# Sheet1.net
KiCad netlist of a schematic drawn in Altium Designer
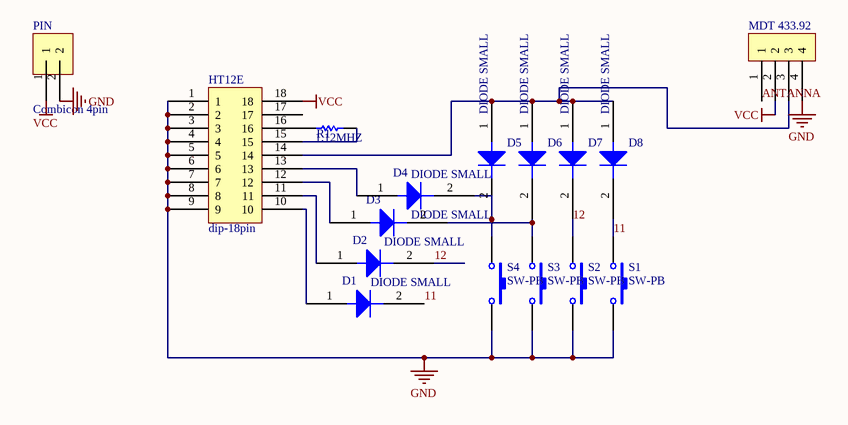
[diagram p0: Sheet1.SchDoc]

(export (version "E")
  (design (tool "Eeschema 10.0.6"))
  (components
    (comp (ref "D1")
      (value "DIODE SMALL")
      (footprint "diode small")
      (libsource (lib "Devindia_v4.0") (part "DIODE SMALL"))
    )
    (comp (ref "D2")
      (value "DIODE SMALL")
      (footprint "diode small")
      (libsource (lib "Devindia_v4.0") (part "DIODE SMALL"))
    )
    (comp (ref "D3")
      (value "DIODE SMALL")
      (footprint "diode small")
      (libsource (lib "Devindia_v4.0") (part "DIODE SMALL"))
    )
    (comp (ref "D4")
      (value "DIODE SMALL")
      (footprint "diode small")
      (libsource (lib "Devindia_v4.0") (part "DIODE SMALL"))
    )
    (comp (ref "D5")
      (value "DIODE SMALL")
      (footprint "diode small")
      (libsource (lib "Devindia_v4.0") (part "DIODE SMALL"))
    )
    (comp (ref "D6")
      (value "DIODE SMALL")
      (footprint "diode small")
      (libsource (lib "Devindia_v4.0") (part "DIODE SMALL"))
    )
    (comp (ref "D7")
      (value "DIODE SMALL")
      (footprint "diode small")
      (libsource (lib "Devindia_v4.0") (part "DIODE SMALL"))
    )
    (comp (ref "D8")
      (value "DIODE SMALL")
      (footprint "diode small")
      (libsource (lib "Devindia_v4.0") (part "DIODE SMALL"))
    )
    (comp (ref "HT12E")
      (value "dip-18pin")
      (footprint "dip-18pin")
      (libsource (lib "Devindia_v4.0") (part "dip-18pin"))
    )
    (comp (ref "MDT 433.92")
      (value "~")
      (footprint "PCBComponent_1")
      (libsource (lib "Schlib1") (part "Component_1"))
    )
    (comp (ref "PIN")
      (value "Combicon 4pin")
      (footprint "combicon-2pin_black")
      (libsource (lib "Devindia_v4.0") (part "Combicon - 2 pin_black"))
    )
    (comp (ref "R1")
      (value "1.12MHZ")
      (footprint "res- 2.54x3")
      (libsource (lib "Devindia_v4.0") (part "Resistor 2.54x3"))
    )
    (comp (ref "S1")
      (value "SW-PB")
      (footprint "sw-pb")
      (description "Switch")
      (fields (field (name "PUBLISHER") "Altium Limited"))
      (libsource (lib "Devindia_v4.0") (part "SW-PB"))
    )
    (comp (ref "S2")
      (value "SW-PB")
      (footprint "sw-pb")
      (description "Switch")
      (fields (field (name "PUBLISHER") "Altium Limited"))
      (libsource (lib "Devindia_v4.0") (part "SW-PB"))
    )
    (comp (ref "S3")
      (value "SW-PB")
      (footprint "sw-pb")
      (description "Switch")
      (fields (field (name "PUBLISHER") "Altium Limited"))
      (libsource (lib "Devindia_v4.0") (part "SW-PB"))
    )
    (comp (ref "S4")
      (value "SW-PB")
      (footprint "sw-pb")
      (description "Switch")
      (fields (field (name "PUBLISHER") "Altium Limited"))
      (libsource (lib "Devindia_v4.0") (part "SW-PB"))
    )
  )
  (nets
    (net (code "1") (name "/11") (class "Default")
      (node (ref "D1") (pin "2") (pinfunction "1_2") (pintype "passive"))
      (node (ref "D8") (pin "2") (pinfunction "1_2") (pintype "passive"))
      (node (ref "S1") (pin "1") (pinfunction "1_1") (pintype "passive"))
    )
    (net (code "2") (name "/12") (class "Default")
      (node (ref "D2") (pin "2") (pinfunction "1_2") (pintype "passive"))
      (node (ref "D7") (pin "2") (pinfunction "1_2") (pintype "passive"))
      (node (ref "S2") (pin "1") (pinfunction "1_1") (pintype "passive"))
    )
    (net (code "3") (name "/ANTANNA") (class "Default")
      (node (ref "MDT 433.92") (pin "1") (pinfunction "1_1") (pintype "passive"))
    )
    (net (code "4") (name "GND") (class "Default")
      (node (ref "HT12E") (pin "1") (pinfunction "1_1") (pintype "passive"))
      (node (ref "HT12E") (pin "2") (pinfunction "2_2") (pintype "passive"))
      (node (ref "HT12E") (pin "3") (pinfunction "3_3") (pintype "passive"))
      (node (ref "HT12E") (pin "4") (pinfunction "4_4") (pintype "passive"))
      (node (ref "HT12E") (pin "5") (pinfunction "5_5") (pintype "passive"))
      (node (ref "HT12E") (pin "6") (pinfunction "6_6") (pintype "passive"))
      (node (ref "HT12E") (pin "7") (pinfunction "7_7") (pintype "passive"))
      (node (ref "HT12E") (pin "8") (pinfunction "8_8") (pintype "passive"))
      (node (ref "HT12E") (pin "9") (pinfunction "9_9") (pintype "passive"))
      (node (ref "MDT 433.92") (pin "4") (pinfunction "4_4") (pintype "passive"))
      (node (ref "PIN") (pin "2") (pinfunction "2_2") (pintype "passive"))
      (node (ref "S1") (pin "2") (pinfunction "2_2") (pintype "passive"))
      (node (ref "S2") (pin "2") (pinfunction "2_2") (pintype "passive"))
      (node (ref "S3") (pin "2") (pinfunction "2_2") (pintype "passive"))
      (node (ref "S4") (pin "2") (pinfunction "2_2") (pintype "passive"))
    )
    (net (code "5") (name "Net-(D1-Pad1)") (class "Default")
      (node (ref "D1") (pin "1") (pinfunction "1_1") (pintype "passive"))
      (node (ref "HT12E") (pin "10") (pinfunction "10_10") (pintype "passive"))
    )
    (net (code "6") (name "Net-(D2-Pad1)") (class "Default")
      (node (ref "D2") (pin "1") (pinfunction "1_1") (pintype "passive"))
      (node (ref "HT12E") (pin "11") (pinfunction "11_11") (pintype "passive"))
    )
    (net (code "7") (name "Net-(D3-1-Pad2)") (class "Default")
      (node (ref "D3") (pin "2") (pinfunction "1_2") (pintype "passive"))
      (node (ref "D6") (pin "2") (pinfunction "1_2") (pintype "passive"))
      (node (ref "S3") (pin "1") (pinfunction "1_1") (pintype "passive"))
    )
    (net (code "8") (name "Net-(D3-Pad1)") (class "Default")
      (node (ref "D3") (pin "1") (pinfunction "1_1") (pintype "passive"))
      (node (ref "HT12E") (pin "12") (pinfunction "12_12") (pintype "passive"))
    )
    (net (code "9") (name "Net-(D4-1-Pad2)") (class "Default")
      (node (ref "D4") (pin "2") (pinfunction "1_2") (pintype "passive"))
      (node (ref "D5") (pin "2") (pinfunction "1_2") (pintype "passive"))
      (node (ref "S4") (pin "1") (pinfunction "1_1") (pintype "passive"))
    )
    (net (code "10") (name "Net-(D4-Pad1)") (class "Default")
      (node (ref "D4") (pin "1") (pinfunction "1_1") (pintype "passive"))
      (node (ref "HT12E") (pin "13") (pinfunction "13_13") (pintype "passive"))
    )
    (net (code "11") (name "Net-(D5-Pad1)") (class "Default")
      (node (ref "D5") (pin "1") (pinfunction "1_1") (pintype "passive"))
      (node (ref "D6") (pin "1") (pinfunction "1_1") (pintype "passive"))
      (node (ref "D7") (pin "1") (pinfunction "1_1") (pintype "passive"))
      (node (ref "D8") (pin "1") (pinfunction "1_1") (pintype "passive"))
      (node (ref "HT12E") (pin "14") (pinfunction "14_14") (pintype "passive"))
      (node (ref "MDT 433.92") (pin "3") (pinfunction "3_3") (pintype "passive"))
    )
    (net (code "12") (name "Net-(HT12E-Pad15)") (class "Default")
      (node (ref "HT12E") (pin "15") (pinfunction "15_15") (pintype "passive"))
      (node (ref "R1") (pin "2") (pinfunction "2_2") (pintype "passive"))
    )
    (net (code "13") (name "Net-(HT12E-Pad16)") (class "Default")
      (node (ref "HT12E") (pin "16") (pinfunction "16_16") (pintype "passive"))
      (node (ref "R1") (pin "1") (pinfunction "1_1") (pintype "passive"))
    )
    (net (code "14") (name "VCC") (class "Default")
      (node (ref "HT12E") (pin "18") (pinfunction "18_18") (pintype "passive"))
      (node (ref "MDT 433.92") (pin "2") (pinfunction "2_2") (pintype "passive"))
      (node (ref "PIN") (pin "1") (pinfunction "1_1") (pintype "passive"))
    )
    (net (code "15") (name "unconnected-(HT12E-Pad17)") (class "Default")
      (node (ref "HT12E") (pin "17") (pinfunction "17_17") (pintype "passive"))
    )
  )
)
